# Electronic_load_front_PCB.net
KiCad netlist of a schematic drawn in EAGLE
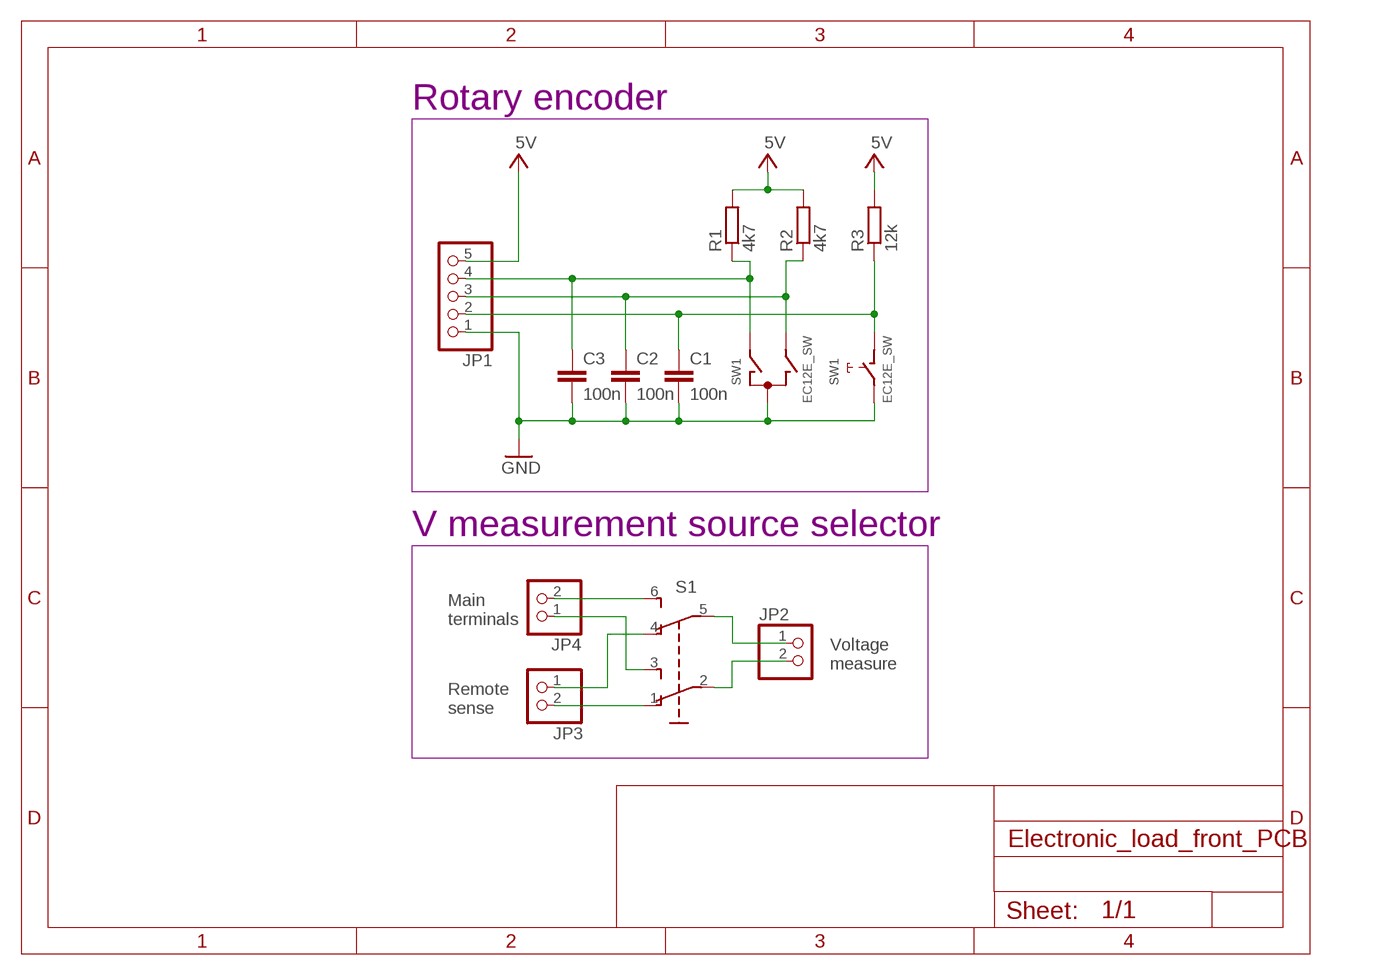
[diagram p0: schematic, sheet 1]

(export (version "E")
  (design (tool "Eeschema 10.0.6"))
  (components
    (comp (ref "C1")
      (value "100n")
      (footprint "eagle-import:C0603")
      (libsource (lib "eagle-import") (part "C-EUC0603"))
    )
    (comp (ref "C2")
      (value "100n")
      (footprint "eagle-import:C0603")
      (libsource (lib "eagle-import") (part "C-EUC0603"))
    )
    (comp (ref "C3")
      (value "100n")
      (footprint "eagle-import:C0603")
      (libsource (lib "eagle-import") (part "C-EUC0603"))
    )
    (comp (ref "JP1")
      (value "PINHD-1X5")
      (footprint "eagle-import:1X05")
      (libsource (lib "eagle-import") (part "PINHD-1X5"))
    )
    (comp (ref "JP2")
      (value "PINHD-1X2/90")
      (footprint "eagle-import:1X02_90")
      (libsource (lib "eagle-import") (part "PINHD-1X2/90"))
    )
    (comp (ref "JP3")
      (value "PINHD-1X2/90")
      (footprint "eagle-import:1X02_90")
      (libsource (lib "eagle-import") (part "PINHD-1X2/90"))
    )
    (comp (ref "JP4")
      (value "PINHD-1X2/90")
      (footprint "eagle-import:1X02_90")
      (libsource (lib "eagle-import") (part "PINHD-1X2/90"))
    )
    (comp (ref "R1")
      (value "4k7")
      (footprint "eagle-import:R0603")
      (libsource (lib "eagle-import") (part "R-EU_R0603"))
    )
    (comp (ref "R2")
      (value "4k7")
      (footprint "eagle-import:R0603")
      (libsource (lib "eagle-import") (part "R-EU_R0603"))
    )
    (comp (ref "R3")
      (value "12k")
      (footprint "eagle-import:R0603")
      (libsource (lib "eagle-import") (part "R-EU_R0603"))
    )
    (comp (ref "S1")
      (value "TL46PO")
      (footprint "eagle-import:TL4XPO")
      (libsource (lib "eagle-import") (part "TL46PO"))
    )
    (comp (ref "SW1")
      (value "EC12E_SW")
      (footprint "eagle-import:ALPS_EC12E_SW")
      (fields (field (name "MPN") "EC12E2424407"))
      (libsource (lib "eagle-import") (part "EC12E_SW"))
    )
  )
  (nets
    (net (code "1") (name "GND") (class "Default")
      (node (ref "C1") (pin "2") (pinfunction "2_2") (pintype "passive"))
      (node (ref "C2") (pin "2") (pinfunction "2_2") (pintype "passive"))
      (node (ref "C3") (pin "2") (pinfunction "2_2") (pintype "passive"))
      (node (ref "JP1") (pin "1") (pinfunction "1_1") (pintype "passive"))
      (node (ref "SW1") (pin "C") (pinfunction "C_C") (pintype "passive"))
      (node (ref "SW1") (pin "E") (pinfunction "2_E") (pintype "passive"))
    )
    (net (code "2") (name "Net-(C2-Pad1)") (class "Default")
      (node (ref "C2") (pin "1") (pinfunction "1_1") (pintype "passive"))
      (node (ref "JP1") (pin "3") (pinfunction "3_3") (pintype "passive"))
      (node (ref "R2") (pin "1") (pinfunction "1_1") (pintype "passive"))
      (node (ref "SW1") (pin "B") (pinfunction "B_B") (pintype "passive"))
    )
    (net (code "3") (name "Net-(C3-Pad1)") (class "Default")
      (node (ref "C3") (pin "1") (pinfunction "1_1") (pintype "passive"))
      (node (ref "JP1") (pin "4") (pinfunction "4_4") (pintype "passive"))
      (node (ref "R1") (pin "1") (pinfunction "1_1") (pintype "passive"))
      (node (ref "SW1") (pin "A") (pinfunction "A_A") (pintype "passive"))
    )
    (net (code "4") (name "Net-(S1-O)") (class "Default")
      (node (ref "JP3") (pin "2") (pinfunction "2_2") (pintype "passive"))
      (node (ref "S1") (pin "1") (pinfunction "O_1") (pintype "passive"))
    )
    (net (code "5") (name "Net-(S1-O1)") (class "Default")
      (node (ref "JP3") (pin "1") (pinfunction "1_1") (pintype "passive"))
      (node (ref "S1") (pin "4") (pinfunction "O1_4") (pintype "passive"))
    )
    (net (code "6") (name "Net-(S1-P)") (class "Default")
      (node (ref "JP2") (pin "2") (pinfunction "2_2") (pintype "passive"))
      (node (ref "S1") (pin "2") (pinfunction "P_2") (pintype "passive"))
    )
    (net (code "7") (name "Net-(S1-P1)") (class "Default")
      (node (ref "JP2") (pin "1") (pinfunction "1_1") (pintype "passive"))
      (node (ref "S1") (pin "5") (pinfunction "P1_5") (pintype "passive"))
    )
    (net (code "8") (name "Net-(S1-S)") (class "Default")
      (node (ref "JP4") (pin "1") (pinfunction "1_1") (pintype "passive"))
      (node (ref "S1") (pin "3") (pinfunction "S_3") (pintype "passive"))
    )
    (net (code "9") (name "Net-(S1-S1)") (class "Default")
      (node (ref "JP4") (pin "2") (pinfunction "2_2") (pintype "passive"))
      (node (ref "S1") (pin "6") (pinfunction "S1_6") (pintype "passive"))
    )
    (net (code "10") (name "Net-(SW1B-1)") (class "Default")
      (node (ref "C1") (pin "1") (pinfunction "1_1") (pintype "passive"))
      (node (ref "JP1") (pin "2") (pinfunction "2_2") (pintype "passive"))
      (node (ref "R3") (pin "1") (pinfunction "1_1") (pintype "passive"))
      (node (ref "SW1") (pin "D") (pinfunction "1_D") (pintype "passive"))
    )
    (net (code "11") (name "VCC") (class "Default")
      (node (ref "JP1") (pin "5") (pinfunction "5_5") (pintype "passive"))
      (node (ref "R1") (pin "2") (pinfunction "2_2") (pintype "passive"))
      (node (ref "R2") (pin "2") (pinfunction "2_2") (pintype "passive"))
      (node (ref "R3") (pin "2") (pinfunction "2_2") (pintype "passive"))
    )
  )
)
